# Controller.net
KiCad netlist of a schematic drawn in Altium Designer
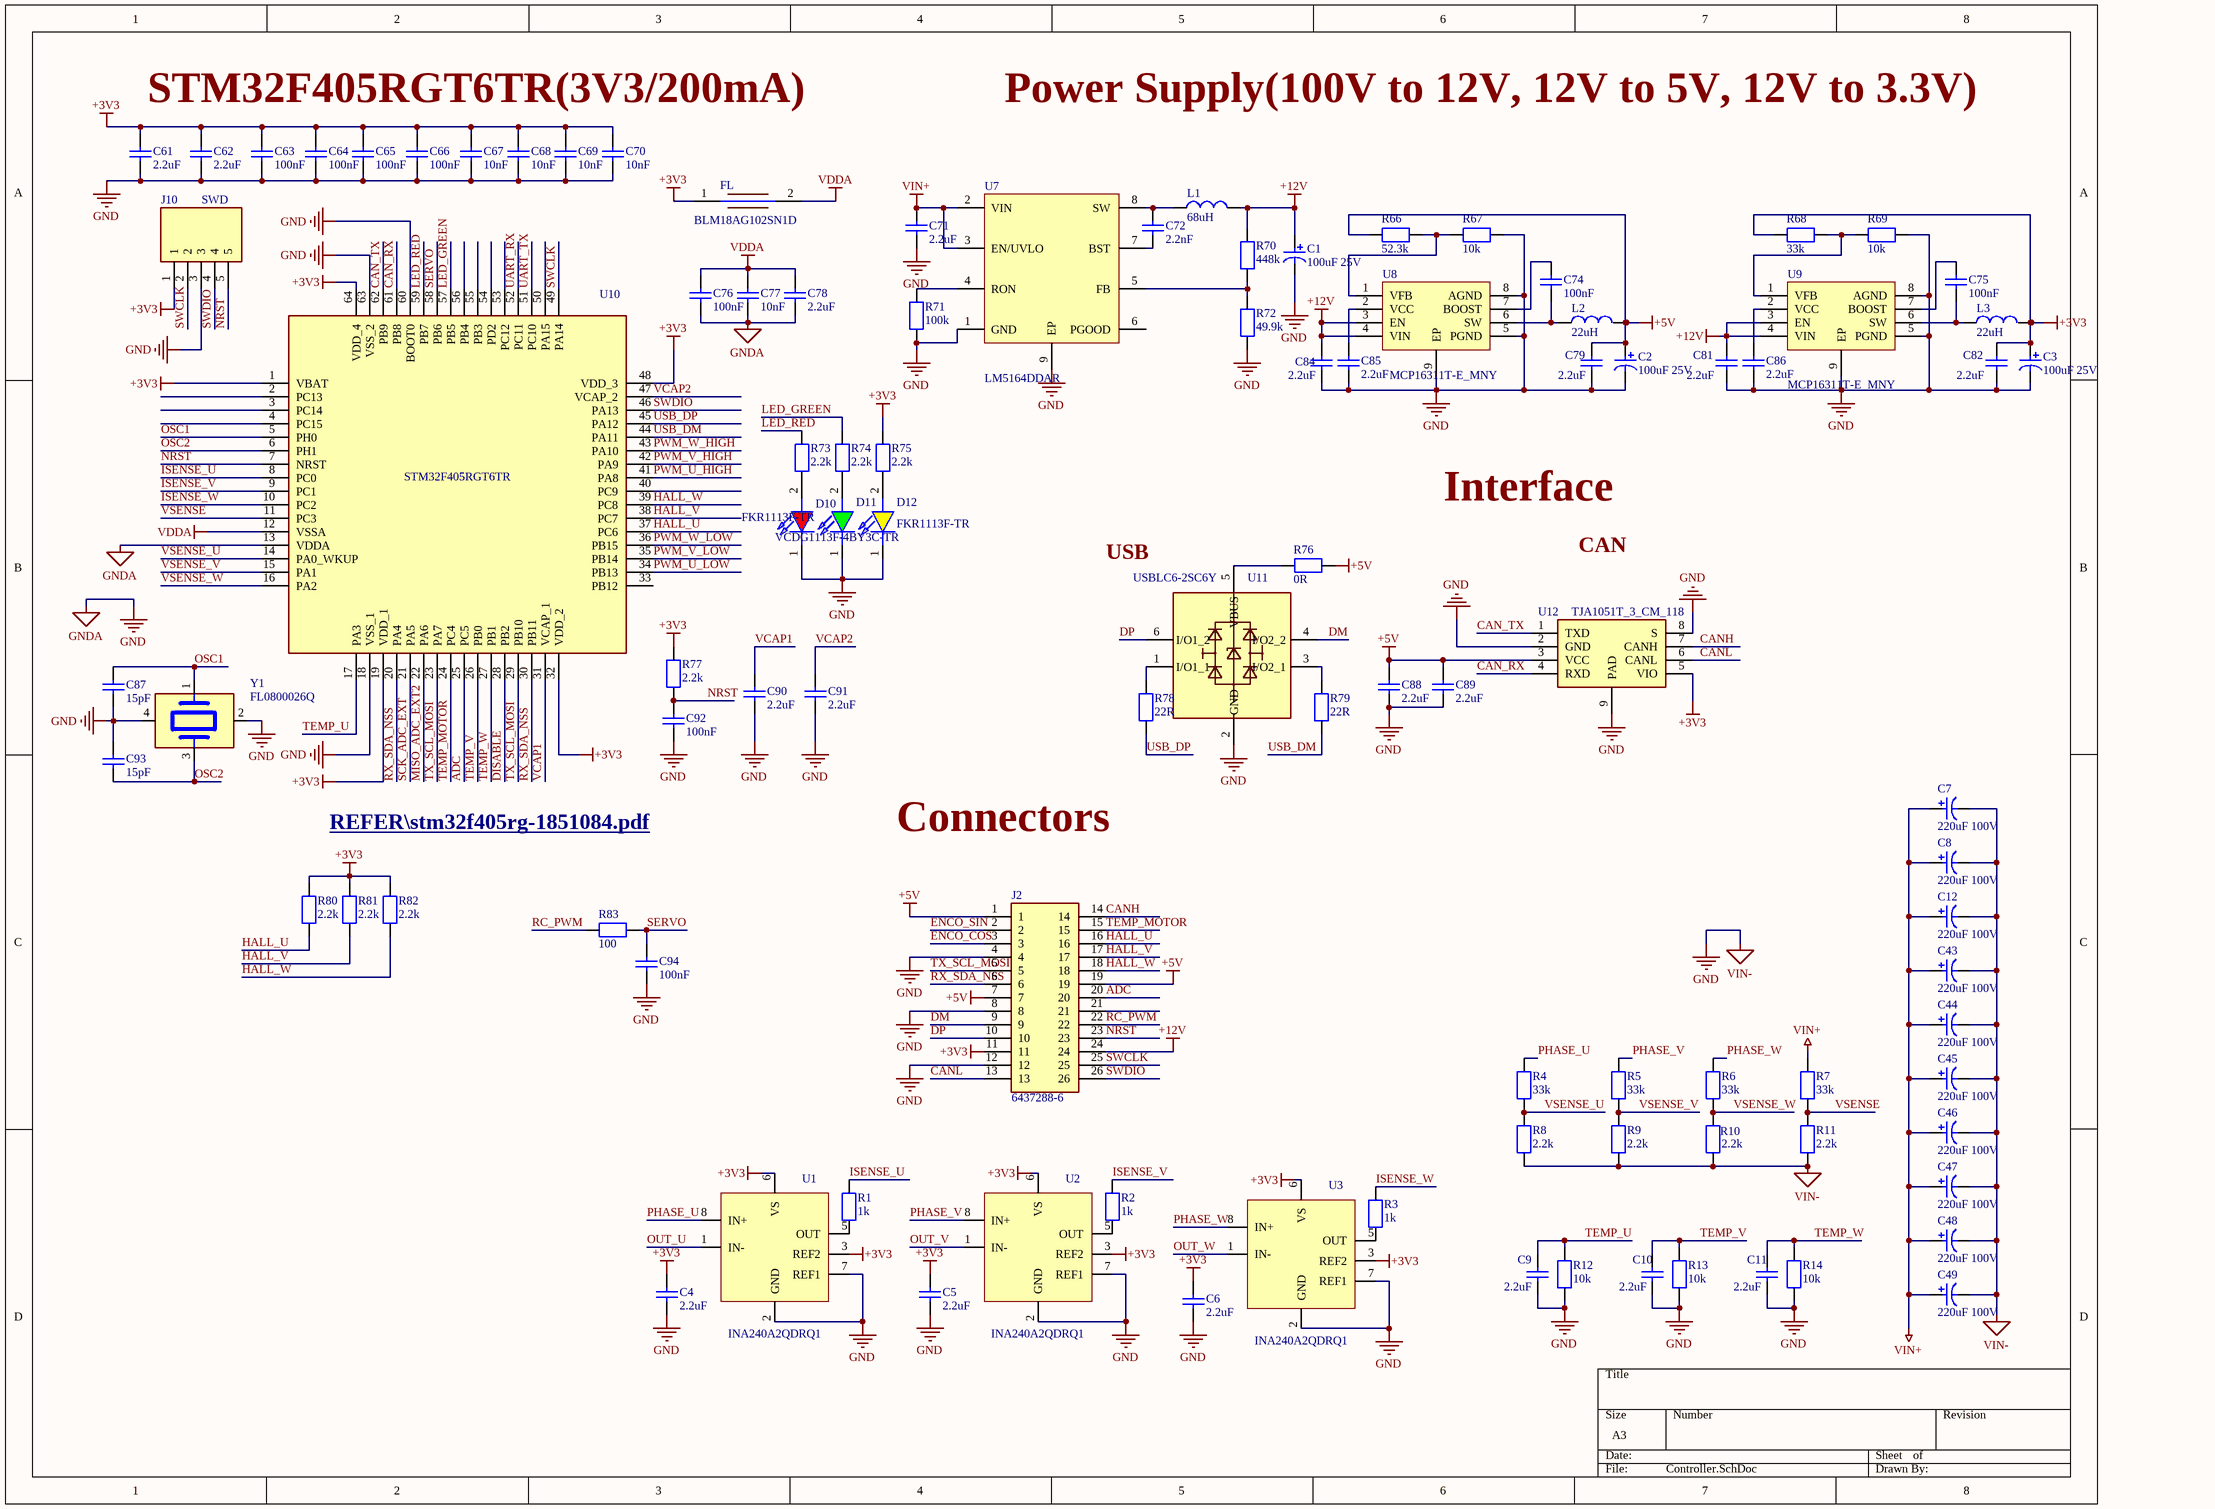
[diagram p0: Controller.SchDoc]

(export (version "E")
  (design (tool "Eeschema 10.0.6"))
  (components
    (comp (ref "C1")
      (value "100uF 25V")
      (footprint "CAPPRD250W50D630H1250")
      (description "100uF ± 10% 25V")
      (fields
        (field (name "MANUFACTURER") "Kemet")
        (field (name "MANUFACTURER PART NUMBER") "ESK107M025AE3AA")
      )
      (libsource (lib "VESC_MotorController") (part "100uF ± 10% 25V"))
    )
    (comp (ref "C2")
      (value "100uF 25V")
      (footprint "CAPPRD250W50D630H1250")
      (description "100uF ± 10% 25V")
      (fields
        (field (name "MANUFACTURER") "Kemet")
        (field (name "MANUFACTURER PART NUMBER") "ESK107M025AE3AA")
      )
      (libsource (lib "VESC_MotorController") (part "100uF ± 10% 25V"))
    )
    (comp (ref "C3")
      (value "100uF 25V")
      (footprint "CAPPRD250W50D630H1250")
      (description "100uF ± 10% 25V")
      (fields
        (field (name "MANUFACTURER") "Kemet")
        (field (name "MANUFACTURER PART NUMBER") "ESK107M025AE3AA")
      )
      (libsource (lib "VESC_MotorController") (part "100uF ± 10% 25V"))
    )
    (comp (ref "C4")
      (value "2.2uF")
      (footprint "C0603")
      (description "2.2uF ± 10% 50V")
      (fields
        (field (name "MANUFACTURER") "Yageo")
        (field (name "MANUFACTURER PART NUMBER") "GRM188R61H225ME11J")
      )
      (libsource (lib "VESC_MotorController") (part "2.2uF ± 10% 50V"))
    )
    (comp (ref "C5")
      (value "2.2uF")
      (footprint "C0603")
      (description "2.2uF ± 10% 50V")
      (fields
        (field (name "MANUFACTURER") "Yageo")
        (field (name "MANUFACTURER PART NUMBER") "GRM188R61H225ME11J")
      )
      (libsource (lib "VESC_MotorController") (part "2.2uF ± 10% 50V"))
    )
    (comp (ref "C6")
      (value "2.2uF")
      (footprint "C0603")
      (description "2.2uF ± 10% 50V")
      (fields
        (field (name "MANUFACTURER") "Yageo")
        (field (name "MANUFACTURER PART NUMBER") "GRM188R61H225ME11J")
      )
      (libsource (lib "VESC_MotorController") (part "2.2uF ± 10% 50V"))
    )
    (comp (ref "C7")
      (value "220uF 100V")
      (footprint "CAPPRD500W65D1250H2200")
      (description "Aluminum Electrolytic Capacitors - Radial Leaded Al Lytic Cap 85C Radial M Series")
      (fields
        (field (name "MANUFACTURER") "Panasonic")
        (field (name "MANUFACTURER PART NUMBER") "ECA-2AM221B")
      )
      (libsource (lib "VESC_MotorController") (part "220uF 100V"))
    )
    (comp (ref "C8")
      (value "220uF 100V")
      (footprint "CAPPRD500W65D1250H2200")
      (description "Aluminum Electrolytic Capacitors - Radial Leaded Al Lytic Cap 85C Radial M Series")
      (fields
        (field (name "MANUFACTURER") "Panasonic")
        (field (name "MANUFACTURER PART NUMBER") "ECA-2AM221B")
      )
      (libsource (lib "VESC_MotorController") (part "220uF 100V"))
    )
    (comp (ref "C9")
      (value "2.2uF")
      (footprint "C0603")
      (description "2.2uF ± 10% 50V")
      (fields
        (field (name "MANUFACTURER") "Yageo")
        (field (name "MANUFACTURER PART NUMBER") "GRM188R61H225ME11J")
      )
      (libsource (lib "VESC_MotorController") (part "2.2uF ± 10% 50V"))
    )
    (comp (ref "C10")
      (value "2.2uF")
      (footprint "C0603")
      (description "2.2uF ± 10% 50V")
      (fields
        (field (name "MANUFACTURER") "Yageo")
        (field (name "MANUFACTURER PART NUMBER") "GRM188R61H225ME11J")
      )
      (libsource (lib "VESC_MotorController") (part "2.2uF ± 10% 50V"))
    )
    (comp (ref "C11")
      (value "2.2uF")
      (footprint "C0603")
      (description "2.2uF ± 10% 50V")
      (fields
        (field (name "MANUFACTURER") "Yageo")
        (field (name "MANUFACTURER PART NUMBER") "GRM188R61H225ME11J")
      )
      (libsource (lib "VESC_MotorController") (part "2.2uF ± 10% 50V"))
    )
    (comp (ref "C12")
      (value "220uF 100V")
      (footprint "CAPPRD500W65D1250H2200")
      (description "Aluminum Electrolytic Capacitors - Radial Leaded Al Lytic Cap 85C Radial M Series")
      (fields
        (field (name "MANUFACTURER") "Panasonic")
        (field (name "MANUFACTURER PART NUMBER") "ECA-2AM221B")
      )
      (libsource (lib "VESC_MotorController") (part "220uF 100V"))
    )
    (comp (ref "C43")
      (value "220uF 100V")
      (footprint "CAPPRD500W65D1250H2200")
      (description "Aluminum Electrolytic Capacitors - Radial Leaded Al Lytic Cap 85C Radial M Series")
      (fields
        (field (name "MANUFACTURER") "Panasonic")
        (field (name "MANUFACTURER PART NUMBER") "ECA-2AM221B")
      )
      (libsource (lib "VESC_MotorController") (part "220uF 100V"))
    )
    (comp (ref "C44")
      (value "220uF 100V")
      (footprint "CAPPRD500W65D1250H2200")
      (description "Aluminum Electrolytic Capacitors - Radial Leaded Al Lytic Cap 85C Radial M Series")
      (fields
        (field (name "MANUFACTURER") "Panasonic")
        (field (name "MANUFACTURER PART NUMBER") "ECA-2AM221B")
      )
      (libsource (lib "VESC_MotorController") (part "220uF 100V"))
    )
    (comp (ref "C45")
      (value "220uF 100V")
      (footprint "CAPPRD500W65D1250H2200")
      (description "Aluminum Electrolytic Capacitors - Radial Leaded Al Lytic Cap 85C Radial M Series")
      (fields
        (field (name "MANUFACTURER") "Panasonic")
        (field (name "MANUFACTURER PART NUMBER") "ECA-2AM221B")
      )
      (libsource (lib "VESC_MotorController") (part "220uF 100V"))
    )
    (comp (ref "C46")
      (value "220uF 100V")
      (footprint "CAPPRD500W65D1250H2200")
      (description "Aluminum Electrolytic Capacitors - Radial Leaded Al Lytic Cap 85C Radial M Series")
      (fields
        (field (name "MANUFACTURER") "Panasonic")
        (field (name "MANUFACTURER PART NUMBER") "ECA-2AM221B")
      )
      (libsource (lib "VESC_MotorController") (part "220uF 100V"))
    )
    (comp (ref "C47")
      (value "220uF 100V")
      (footprint "CAPPRD500W65D1250H2200")
      (description "Aluminum Electrolytic Capacitors - Radial Leaded Al Lytic Cap 85C Radial M Series")
      (fields
        (field (name "MANUFACTURER") "Panasonic")
        (field (name "MANUFACTURER PART NUMBER") "ECA-2AM221B")
      )
      (libsource (lib "VESC_MotorController") (part "220uF 100V"))
    )
    (comp (ref "C48")
      (value "220uF 100V")
      (footprint "CAPPRD500W65D1250H2200")
      (description "Aluminum Electrolytic Capacitors - Radial Leaded Al Lytic Cap 85C Radial M Series")
      (fields
        (field (name "MANUFACTURER") "Panasonic")
        (field (name "MANUFACTURER PART NUMBER") "ECA-2AM221B")
      )
      (libsource (lib "VESC_MotorController") (part "220uF 100V"))
    )
    (comp (ref "C49")
      (value "220uF 100V")
      (footprint "CAPPRD500W65D1250H2200")
      (description "Aluminum Electrolytic Capacitors - Radial Leaded Al Lytic Cap 85C Radial M Series")
      (fields
        (field (name "MANUFACTURER") "Panasonic")
        (field (name "MANUFACTURER PART NUMBER") "ECA-2AM221B")
      )
      (libsource (lib "VESC_MotorController") (part "220uF 100V"))
    )
    (comp (ref "C61")
      (value "2.2uF")
      (footprint "C0603")
      (description "2.2uF ± 10% 50V")
      (fields
        (field (name "MANUFACTURER") "Yageo")
        (field (name "MANUFACTURER PART NUMBER") "GRM188R61H225ME11J")
      )
      (libsource (lib "VESC_MotorController") (part "2.2uF ± 10% 50V"))
    )
    (comp (ref "C62")
      (value "2.2uF")
      (footprint "C0603")
      (description "2.2uF ± 10% 50V")
      (fields
        (field (name "MANUFACTURER") "Yageo")
        (field (name "MANUFACTURER PART NUMBER") "GRM188R61H225ME11J")
      )
      (libsource (lib "VESC_MotorController") (part "2.2uF ± 10% 50V"))
    )
    (comp (ref "C63")
      (value "100nF")
      (footprint "C0603")
      (description "100nF ± 10% 50V")
      (fields
        (field (name "MANUFACTURER") "Yageo")
        (field (name "MANUFACTURER PART NUMBER") "CS0603KRX7R9BB104")
      )
      (libsource (lib "VESC_MotorController") (part "100nF ± 10% 50V"))
    )
    (comp (ref "C64")
      (value "100nF")
      (footprint "C0603")
      (description "100nF ± 10% 50V")
      (fields
        (field (name "MANUFACTURER") "Yageo")
        (field (name "MANUFACTURER PART NUMBER") "CS0603KRX7R9BB104")
      )
      (libsource (lib "VESC_MotorController") (part "100nF ± 10% 50V"))
    )
    (comp (ref "C65")
      (value "100nF")
      (footprint "C0603")
      (description "100nF ± 10% 50V")
      (fields
        (field (name "MANUFACTURER") "Yageo")
        (field (name "MANUFACTURER PART NUMBER") "CS0603KRX7R9BB104")
      )
      (libsource (lib "VESC_MotorController") (part "100nF ± 10% 50V"))
    )
    (comp (ref "C66")
      (value "100nF")
      (footprint "C0603")
      (description "100nF ± 10% 50V")
      (fields
        (field (name "MANUFACTURER") "Yageo")
        (field (name "MANUFACTURER PART NUMBER") "CS0603KRX7R9BB104")
      )
      (libsource (lib "VESC_MotorController") (part "100nF ± 10% 50V"))
    )
    (comp (ref "C67")
      (value "10nF")
      (footprint "C0603")
      (description "10nF ± 10% 50V")
      (fields
        (field (name "MANUFACTURER") "Yageo")
        (field (name "MANUFACTURER PART NUMBER") "CS0603KRX79BB103")
      )
      (libsource (lib "VESC_MotorController") (part "10nF ± 10% 50V"))
    )
    (comp (ref "C68")
      (value "10nF")
      (footprint "C0603")
      (description "10nF ± 10% 50V")
      (fields
        (field (name "MANUFACTURER") "Yageo")
        (field (name "MANUFACTURER PART NUMBER") "CS0603KRX79BB103")
      )
      (libsource (lib "VESC_MotorController") (part "10nF ± 10% 50V"))
    )
    (comp (ref "C69")
      (value "10nF")
      (footprint "C0603")
      (description "10nF ± 10% 50V")
      (fields
        (field (name "MANUFACTURER") "Yageo")
        (field (name "MANUFACTURER PART NUMBER") "CS0603KRX79BB103")
      )
      (libsource (lib "VESC_MotorController") (part "10nF ± 10% 50V"))
    )
    (comp (ref "C70")
      (value "10nF")
      (footprint "C0603")
      (description "10nF ± 10% 50V")
      (fields
        (field (name "MANUFACTURER") "Yageo")
        (field (name "MANUFACTURER PART NUMBER") "CS0603KRX79BB103")
      )
      (libsource (lib "VESC_MotorController") (part "10nF ± 10% 50V"))
    )
    (comp (ref "C71")
      (value "2.2uF")
      (footprint "C0603")
      (description "2.2uF ± 10% 50V")
      (fields
        (field (name "MANUFACTURER") "Yageo")
        (field (name "MANUFACTURER PART NUMBER") "GRM188R61H225ME11J")
      )
      (libsource (lib "VESC_MotorController") (part "2.2uF ± 10% 50V"))
    )
    (comp (ref "C72")
      (value "2.2nF")
      (footprint "C0603")
      (description "2.2nF ± 10% 50V")
      (fields
        (field (name "MANUFACTURER") "Yageo")
        (field (name "MANUFACTURER PART NUMBER") "CS0603KRX79BB222")
      )
      (libsource (lib "VESC_MotorController") (part "2.2nF ± 10% 50V"))
    )
    (comp (ref "C74")
      (value "100nF")
      (footprint "C0603")
      (description "100nF ± 10% 50V")
      (fields
        (field (name "MANUFACTURER") "Yageo")
        (field (name "MANUFACTURER PART NUMBER") "CS0603KRX7R9BB104")
      )
      (libsource (lib "VESC_MotorController") (part "100nF ± 10% 50V"))
    )
    (comp (ref "C75")
      (value "100nF")
      (footprint "C0603")
      (description "100nF ± 10% 50V")
      (fields
        (field (name "MANUFACTURER") "Yageo")
        (field (name "MANUFACTURER PART NUMBER") "CS0603KRX7R9BB104")
      )
      (libsource (lib "VESC_MotorController") (part "100nF ± 10% 50V"))
    )
    (comp (ref "C76")
      (value "100nF")
      (footprint "C0603")
      (description "100nF ± 10% 50V")
      (fields
        (field (name "MANUFACTURER") "Yageo")
        (field (name "MANUFACTURER PART NUMBER") "CS0603KRX7R9BB104")
      )
      (libsource (lib "VESC_MotorController") (part "100nF ± 10% 50V"))
    )
    (comp (ref "C77")
      (value "10nF")
      (footprint "C0603")
      (description "10nF ± 10% 50V")
      (fields
        (field (name "MANUFACTURER") "Yageo")
        (field (name "MANUFACTURER PART NUMBER") "CS0603KRX79BB103")
      )
      (libsource (lib "VESC_MotorController") (part "10nF ± 10% 50V"))
    )
    (comp (ref "C78")
      (value "2.2uF")
      (footprint "C0603")
      (description "2.2uF ± 10% 50V")
      (fields
        (field (name "MANUFACTURER") "Yageo")
        (field (name "MANUFACTURER PART NUMBER") "GRM188R61H225ME11J")
      )
      (libsource (lib "VESC_MotorController") (part "2.2uF ± 10% 50V"))
    )
    (comp (ref "C79")
      (value "2.2uF")
      (footprint "C0603")
      (description "2.2uF ± 10% 50V")
      (fields
        (field (name "MANUFACTURER") "Yageo")
        (field (name "MANUFACTURER PART NUMBER") "GRM188R61H225ME11J")
      )
      (libsource (lib "VESC_MotorController") (part "2.2uF ± 10% 50V"))
    )
    (comp (ref "C81")
      (value "2.2uF")
      (footprint "C0603")
      (description "2.2uF ± 10% 50V")
      (fields
        (field (name "MANUFACTURER") "Yageo")
        (field (name "MANUFACTURER PART NUMBER") "GRM188R61H225ME11J")
      )
      (libsource (lib "VESC_MotorController") (part "2.2uF ± 10% 50V"))
    )
    (comp (ref "C82")
      (value "2.2uF")
      (footprint "C0603")
      (description "2.2uF ± 10% 50V")
      (fields
        (field (name "MANUFACTURER") "Yageo")
        (field (name "MANUFACTURER PART NUMBER") "GRM188R61H225ME11J")
      )
      (libsource (lib "VESC_MotorController") (part "2.2uF ± 10% 50V"))
    )
    (comp (ref "C84")
      (value "2.2uF")
      (footprint "C0603")
      (description "2.2uF ± 10% 50V")
      (fields
        (field (name "MANUFACTURER") "Yageo")
        (field (name "MANUFACTURER PART NUMBER") "GRM188R61H225ME11J")
      )
      (libsource (lib "VESC_MotorController") (part "2.2uF ± 10% 50V"))
    )
    (comp (ref "C85")
      (value "2.2uF")
      (footprint "C0603")
      (description "2.2uF ± 10% 50V")
      (fields
        (field (name "MANUFACTURER") "Yageo")
        (field (name "MANUFACTURER PART NUMBER") "GRM188R61H225ME11J")
      )
      (libsource (lib "VESC_MotorController") (part "2.2uF ± 10% 50V"))
    )
    (comp (ref "C86")
      (value "2.2uF")
      (footprint "C0603")
      (description "2.2uF ± 10% 50V")
      (fields
        (field (name "MANUFACTURER") "Yageo")
        (field (name "MANUFACTURER PART NUMBER") "GRM188R61H225ME11J")
      )
      (libsource (lib "VESC_MotorController") (part "2.2uF ± 10% 50V"))
    )
    (comp (ref "C87")
      (value "15pF")
      (footprint "C0402")
      (description "15pF ± 10% 50V")
      (fields
        (field (name "MANUFACTURER") "Yageo")
        (field (name "MANUFACTURER PART NUMBER") "CS0603KRX79BB150")
      )
      (libsource (lib "VESC_MotorController") (part "15pF ± 10% 50V"))
    )
    (comp (ref "C88")
      (value "2.2uF")
      (footprint "C0603")
      (description "2.2uF ± 10% 50V")
      (fields
        (field (name "MANUFACTURER") "Yageo")
        (field (name "MANUFACTURER PART NUMBER") "GRM188R61H225ME11J")
      )
      (libsource (lib "VESC_MotorController") (part "2.2uF ± 10% 50V"))
    )
    (comp (ref "C89")
      (value "2.2uF")
      (footprint "C0603")
      (description "2.2uF ± 10% 50V")
      (fields
        (field (name "MANUFACTURER") "Yageo")
        (field (name "MANUFACTURER PART NUMBER") "GRM188R61H225ME11J")
      )
      (libsource (lib "VESC_MotorController") (part "2.2uF ± 10% 50V"))
    )
    (comp (ref "C90")
      (value "2.2uF")
      (footprint "C0603")
      (description "2.2uF ± 10% 50V")
      (fields
        (field (name "MANUFACTURER") "Yageo")
        (field (name "MANUFACTURER PART NUMBER") "GRM188R61H225ME11J")
      )
      (libsource (lib "VESC_MotorController") (part "2.2uF ± 10% 50V"))
    )
    (comp (ref "C91")
      (value "2.2uF")
      (footprint "C0603")
      (description "2.2uF ± 10% 50V")
      (fields
        (field (name "MANUFACTURER") "Yageo")
        (field (name "MANUFACTURER PART NUMBER") "GRM188R61H225ME11J")
      )
      (libsource (lib "VESC_MotorController") (part "2.2uF ± 10% 50V"))
    )
    (comp (ref "C92")
      (value "100nF")
      (footprint "C0603")
      (description "100nF ± 10% 50V")
      (fields
        (field (name "MANUFACTURER") "Yageo")
        (field (name "MANUFACTURER PART NUMBER") "CS0603KRX7R9BB104")
      )
      (libsource (lib "VESC_MotorController") (part "100nF ± 10% 50V"))
    )
    (comp (ref "C93")
      (value "15pF")
      (footprint "C0402")
      (description "15pF ± 10% 50V")
      (fields
        (field (name "MANUFACTURER") "Yageo")
        (field (name "MANUFACTURER PART NUMBER") "CS0603KRX79BB150")
      )
      (libsource (lib "VESC_MotorController") (part "15pF ± 10% 50V"))
    )
    (comp (ref "C94")
      (value "100nF")
      (footprint "C0603")
      (description "100nF ± 10% 50V")
      (fields
        (field (name "MANUFACTURER") "Yageo")
        (field (name "MANUFACTURER PART NUMBER") "CS0603KRX7R9BB104")
      )
      (libsource (lib "VESC_MotorController") (part "100nF ± 10% 50V"))
    )
    (comp (ref "D10")
      (value "FKR1113F-TR")
      (footprint "VCDG1113F4BY3CTR")
      (description "R/A LED")
      (fields (field (name "MANUFACTURER") "Stanley Electric"))
      (libsource (lib "VESC_MotorController") (part "LED_RED"))
    )
    (comp (ref "D11")
      (value "VCDG1113F-4BY3C-TR")
      (footprint "VCDG1113F4BY3CTR")
      (description "R/A LED")
      (fields (field (name "MANUFACTURER") "Stanley Electric"))
      (libsource (lib "VESC_MotorController") (part "LED_GREEN"))
    )
    (comp (ref "D12")
      (value "FKR1113F-TR")
      (footprint "VCDG1113F4BY3CTR")
      (description "R/A LED")
      (fields
        (field (name "MANUFACTURER") "Stanley Electric")
        (field (name "MANUFACTURER PART NUMBER") "FKY1113F-TR")
      )
      (libsource (lib "VESC_MotorController") (part "LED_YELLOW"))
    )
    (comp (ref "FL")
      (value "BLM18AG102SN1D")
      (footprint "BLM18EG121SH1D")
      (description "Ferrite Beads 1000 OHM 25% Alternate Sizing Guide Below")
      (fields (field (name "MANUFACTURER") "Murata"))
      (libsource (lib "VESC_MotorController") (part "BLM18AG102SN1D"))
    )
    (comp (ref "J2")
      (value "6437288-6")
      (footprint "64372886")
      (description "Header vert 26 way 4 row Tab Superseal")
      (fields (field (name "MANUFACTURER") "TE Connectivity"))
      (libsource (lib "VESC_MotorController") (part "6437288-6"))
    )
    (comp (ref "J10")
      (value "SWD")
      (footprint "61300511021")
      (description "Headers & Wire Housings WR-PHD 2.54mm Hdr 5P Single RA Gold")
      (fields
        (field (name "MANUFACTURER") "Wurth Electronic")
        (field (name "MANUFACTURER PART NUMBER") "61300511021")
      )
      (libsource (lib "VESC_MotorController") (part "Header 5 Pin_1"))
    )
    (comp (ref "L1")
      (value "68uH")
      (footprint "INDPM7973X540N")
      (description "Ind,7.9x7.3x5.2mm,68uH+/-20%,2.7A,shd")
      (fields
        (field (name "MANUFACTURER") "Bourns")
        (field (name "MANUFACTURER PART NUMBER") "SRP7050WA-680M")
      )
      (libsource (lib "VESC_MotorController") (part "SRP7050WA-680M"))
    )
    (comp (ref "L2")
      (value "22uH")
      (footprint "INDPM7973X540N")
      (description "Ind,7.9x7.3x5.2mm,22uH+/-20%,5A,shd")
      (fields
        (field (name "MANUFACTURER") "Bourns")
        (field (name "MANUFACTURER PART NUMBER") "SRP7050WA-220M")
      )
      (libsource (lib "VESC_MotorController") (part "SRP7050WA-220M"))
    )
    (comp (ref "L3")
      (value "22uH")
      (footprint "INDPM7973X540N")
      (description "Ind,7.9x7.3x5.2mm,22uH+/-20%,5A,shd")
      (fields
        (field (name "MANUFACTURER") "Bourns")
        (field (name "MANUFACTURER PART NUMBER") "SRP7050WA-220M")
      )
      (libsource (lib "VESC_MotorController") (part "SRP7050WA-220M"))
    )
    (comp (ref "R1")
      (value "1k")
      (footprint "R0603")
      (description "1 kOhms ±1% 0.1W")
      (fields
        (field (name "MANUFACTURER") "Yageo")
        (field (name "MANUFACTURER PART NUMBER") "RC0603FR-071KL")
      )
      (libsource (lib "VESC_MotorController") (part "1 kOhms ±1% 0.1W"))
    )
    (comp (ref "R2")
      (value "1k")
      (footprint "R0603")
      (description "1 kOhms ±1% 0.1W")
      (fields
        (field (name "MANUFACTURER") "Yageo")
        (field (name "MANUFACTURER PART NUMBER") "RC0603FR-071KL")
      )
      (libsource (lib "VESC_MotorController") (part "1 kOhms ±1% 0.1W"))
    )
    (comp (ref "R3")
      (value "1k")
      (footprint "R0603")
      (description "1 kOhms ±1% 0.1W")
      (fields
        (field (name "MANUFACTURER") "Yageo")
        (field (name "MANUFACTURER PART NUMBER") "RC0603FR-071KL")
      )
      (libsource (lib "VESC_MotorController") (part "1 kOhms ±1% 0.1W"))
    )
    (comp (ref "R4")
      (value "33k")
      (footprint "R0603")
      (description "33 kOhms ±1% 0.1W")
      (fields
        (field (name "MANUFACTURER") "Yageo")
        (field (name "MANUFACTURER PART NUMBER") "RC0603FR-0733KL")
      )
      (libsource (lib "VESC_MotorController") (part "33 kOhms ±1% 0.1W"))
    )
    (comp (ref "R5")
      (value "33k")
      (footprint "R0603")
      (description "33 kOhms ±1% 0.1W")
      (fields
        (field (name "MANUFACTURER") "Yageo")
        (field (name "MANUFACTURER PART NUMBER") "RC0603FR-0733KL")
      )
      (libsource (lib "VESC_MotorController") (part "33 kOhms ±1% 0.1W"))
    )
    (comp (ref "R6")
      (value "33k")
      (footprint "R0603")
      (description "33 kOhms ±1% 0.1W")
      (fields
        (field (name "MANUFACTURER") "Yageo")
        (field (name "MANUFACTURER PART NUMBER") "RC0603FR-0733KL")
      )
      (libsource (lib "VESC_MotorController") (part "33 kOhms ±1% 0.1W"))
    )
    (comp (ref "R7")
      (value "33k")
      (footprint "R0603")
      (description "33 kOhms ±1% 0.1W")
      (fields
        (field (name "MANUFACTURER") "Yageo")
        (field (name "MANUFACTURER PART NUMBER") "RC0603FR-0733KL")
      )
      (libsource (lib "VESC_MotorController") (part "33 kOhms ±1% 0.1W"))
    )
    (comp (ref "R8")
      (value "2.2k")
      (footprint "R0603")
      (description "2.2 kOhms ±1% 0.1W")
      (fields
        (field (name "MANUFACTURER") "Yageo")
        (field (name "MANUFACTURER PART NUMBER") "RC0603FR-072K2L")
      )
      (libsource (lib "VESC_MotorController") (part "2.2 kOhms ±1% 0.1W"))
    )
    (comp (ref "R9")
      (value "2.2k")
      (footprint "R0603")
      (description "2.2 kOhms ±1% 0.1W")
      (fields
        (field (name "MANUFACTURER") "Yageo")
        (field (name "MANUFACTURER PART NUMBER") "RC0603FR-072K2L")
      )
      (libsource (lib "VESC_MotorController") (part "2.2 kOhms ±1% 0.1W"))
    )
    (comp (ref "R10")
      (value "2.2k")
      (footprint "R0603")
      (description "2.2 kOhms ±1% 0.1W")
      (fields
        (field (name "MANUFACTURER") "Yageo")
        (field (name "MANUFACTURER PART NUMBER") "RC0603FR-072K2L")
      )
      (libsource (lib "VESC_MotorController") (part "2.2 kOhms ±1% 0.1W"))
    )
    (comp (ref "R11")
      (value "2.2k")
      (footprint "R0603")
      (description "2.2 kOhms ±1% 0.1W")
      (fields
        (field (name "MANUFACTURER") "Yageo")
        (field (name "MANUFACTURER PART NUMBER") "RC0603FR-072K2L")
      )
      (libsource (lib "VESC_MotorController") (part "2.2 kOhms ±1% 0.1W"))
    )
    (comp (ref "R12")
      (value "10k")
      (footprint "R0603")
      (description "10 kOhms ±1% 0.1W")
      (fields
        (field (name "MANUFACTURER") "Yageo")
        (field (name "MANUFACTURER PART NUMBER") "RC0603FR-0710KL")
      )
      (libsource (lib "VESC_MotorController") (part "10 kOhms ±1% 0.1W"))
    )
    (comp (ref "R13")
      (value "10k")
      (footprint "R0603")
      (description "10 kOhms ±1% 0.1W")
      (fields
        (field (name "MANUFACTURER") "Yageo")
        (field (name "MANUFACTURER PART NUMBER") "RC0603FR-0710KL")
      )
      (libsource (lib "VESC_MotorController") (part "10 kOhms ±1% 0.1W"))
    )
    (comp (ref "R14")
      (value "10k")
      (footprint "R0603")
      (description "10 kOhms ±1% 0.1W")
      (fields
        (field (name "MANUFACTURER") "Yageo")
        (field (name "MANUFACTURER PART NUMBER") "RC0603FR-0710KL")
      )
      (libsource (lib "VESC_MotorController") (part "10 kOhms ±1% 0.1W"))
    )
    (comp (ref "R66")
      (value "52.3k")
      (footprint "R0603")
      (description "52.3 kOhms ±1% 0.1W")
      (fields
        (field (name "MANUFACTURER") "Yageo")
        (field (name "MANUFACTURER PART NUMBER") "RC0603FR-0752K3L")
      )
      (libsource (lib "VESC_MotorController") (part "52.3 kOhms ±1% 0.1W"))
    )
    (comp (ref "R67")
      (value "10k")
      (footprint "R0603")
      (description "10 kOhms ±1% 0.1W")
      (fields
        (field (name "MANUFACTURER") "Yageo")
        (field (name "MANUFACTURER PART NUMBER") "RC0603FR-0710KL")
      )
      (libsource (lib "VESC_MotorController") (part "10 kOhms ±1% 0.1W"))
    )
    (comp (ref "R68")
      (value "33k")
      (footprint "R0603")
      (description "33 kOhms ±1% 0.1W")
      (fields
        (field (name "MANUFACTURER") "Yageo")
        (field (name "MANUFACTURER PART NUMBER") "RC0603FR-0733KL")
      )
      (libsource (lib "VESC_MotorController") (part "33 kOhms ±1% 0.1W"))
    )
    (comp (ref "R69")
      (value "10k")
      (footprint "R0603")
      (description "10 kOhms ±1% 0.1W")
      (fields
        (field (name "MANUFACTURER") "Yageo")
        (field (name "MANUFACTURER PART NUMBER") "RC0603FR-0710KL")
      )
      (libsource (lib "VESC_MotorController") (part "10 kOhms ±1% 0.1W"))
    )
    (comp (ref "R70")
      (value "448k")
      (footprint "R0603")
      (description "448 kOhms ±1% 0.1W")
      (fields
        (field (name "MANUFACTURER") "Yageo")
        (field (name "MANUFACTURER PART NUMBER") "RC0603FR-07448KL")
      )
      (libsource (lib "VESC_MotorController") (part "448 kOhms ±1% 0.1W"))
    )
    (comp (ref "R71")
      (value "100k")
      (footprint "R0603")
      (description "100 kOhms ±1% 0.1W")
      (fields
        (field (name "MANUFACTURER") "Yageo")
        (field (name "MANUFACTURER PART NUMBER") "RC0603FR-07100KL")
      )
      (libsource (lib "VESC_MotorController") (part "100 kOhms ±1% 0.1W"))
    )
    (comp (ref "R72")
      (value "49.9k")
      (footprint "R0603")
      (description "49.9 kOhms ±1% 0.1W")
      (fields
        (field (name "MANUFACTURER") "Yageo")
        (field (name "MANUFACTURER PART NUMBER") "RC0603FR-0749K9L")
      )
      (libsource (lib "VESC_MotorController") (part "49.9 kOhms ±1% 0.1W"))
    )
    (comp (ref "R73")
      (value "2.2k")
      (footprint "R0603")
      (description "2.2 kOhms ±1% 0.1W")
      (fields
        (field (name "MANUFACTURER") "Yageo")
        (field (name "MANUFACTURER PART NUMBER") "RC0603FR-072K2L")
      )
      (libsource (lib "VESC_MotorController") (part "2.2 kOhms ±1% 0.1W"))
    )
    (comp (ref "R74")
      (value "2.2k")
      (footprint "R0603")
      (description "2.2 kOhms ±1% 0.1W")
      (fields
        (field (name "MANUFACTURER") "Yageo")
        (field (name "MANUFACTURER PART NUMBER") "RC0603FR-072K2L")
      )
      (libsource (lib "VESC_MotorController") (part "2.2 kOhms ±1% 0.1W"))
    )
    (comp (ref "R75")
      (value "2.2k")
      (footprint "R0603")
      (description "2.2 kOhms ±1% 0.1W")
      (fields
        (field (name "MANUFACTURER") "Yageo")
        (field (name "MANUFACTURER PART NUMBER") "RC0603FR-072K2L")
      )
      (libsource (lib "VESC_MotorController") (part "2.2 kOhms ±1% 0.1W"))
    )
    (comp (ref "R76")
      (value "0R")
      (footprint "R1206")
      (description "0 ohm 0.25W ±1%")
      (fields
        (field (name "MANUFACTURER PART NUMBER") "RC1206FR-070RL")
        (field (name "MANUFACTURER") "Yageo")
      )
      (libsource (lib "VESC_MotorController") (part "0ohm 0.25W ±1%"))
    )
    (comp (ref "R77")
      (value "2.2k")
      (footprint "R0603")
      (description "2.2 kOhms ±1% 0.1W")
      (fields
        (field (name "MANUFACTURER") "Yageo")
        (field (name "MANUFACTURER PART NUMBER") "RC0603FR-072K2L")
      )
      (libsource (lib "VESC_MotorController") (part "2.2 kOhms ±1% 0.1W"))
    )
    (comp (ref "R78")
      (value "22R")
      (footprint "R0603")
      (description "22 ohm 0.1W ±1%")
      (fields
        (field (name "MANUFACTURER PART NUMBER") "RC0603FR-0722RL")
        (field (name "MANUFACTURER") "Yageo")
      )
      (libsource (lib "VESC_MotorController") (part "22ohm 0.1W ±1%"))
    )
    (comp (ref "R79")
      (value "22R")
      (footprint "R0603")
      (description "22 ohm 0.1W ±1%")
      (fields
        (field (name "MANUFACTURER PART NUMBER") "RC0603FR-0722RL")
        (field (name "MANUFACTURER") "Yageo")
      )
      (libsource (lib "VESC_MotorController") (part "22ohm 0.1W ±1%"))
    )
    (comp (ref "R80")
      (value "2.2k")
      (footprint "R0603")
      (description "2.2 kOhms ±1% 0.1W")
      (fields
        (field (name "MANUFACTURER") "Yageo")
        (field (name "MANUFACTURER PART NUMBER") "RC0603FR-072K2L")
      )
      (libsource (lib "VESC_MotorController") (part "2.2 kOhms ±1% 0.1W"))
    )
    (comp (ref "R81")
      (value "2.2k")
      (footprint "R0603")
      (description "2.2 kOhms ±1% 0.1W")
      (fields
        (field (name "MANUFACTURER") "Yageo")
        (field (name "MANUFACTURER PART NUMBER") "RC0603FR-072K2L")
      )
      (libsource (lib "VESC_MotorController") (part "2.2 kOhms ±1% 0.1W"))
    )
    (comp (ref "R82")
      (value "2.2k")
      (footprint "R0603")
      (description "2.2 kOhms ±1% 0.1W")
      (fields
        (field (name "MANUFACTURER") "Yageo")
        (field (name "MANUFACTURER PART NUMBER") "RC0603FR-072K2L")
      )
      (libsource (lib "VESC_MotorController") (part "2.2 kOhms ±1% 0.1W"))
    )
    (comp (ref "R83")
      (value "100")
      (footprint "R0603")
      (description "100 Ohms ±1% 0.1W")
      (fields
        (field (name "MANUFACTURER") "Yageo")
        (field (name "MANUFACTURER PART NUMBER") "RC0603FR-0710KL")
      )
      (libsource (lib "VESC_MotorController") (part "100 Ohms ±1% 0.1W"))
    )
    (comp (ref "U1")
      (value "INA240A2QDRQ1")
      (footprint "SOIC127P600X175-8N")
      (description "Automotive, High/Low Side, Bi-Directional Zer-Drift Current Sense Amp w/ Enhanced PWM Rejection")
      (fields (field (name "MANUFACTURER") "Texas Instruments"))
      (libsource (lib "VESC_MotorController") (part "INA240A2QDRQ1"))
    )
    (comp (ref "U2")
      (value "INA240A2QDRQ1")
      (footprint "SOIC127P600X175-8N")
      (description "Automotive, High/Low Side, Bi-Directional Zer-Drift Current Sense Amp w/ Enhanced PWM Rejection")
      (fields (field (name "MANUFACTURER") "Texas Instruments"))
      (libsource (lib "VESC_MotorController") (part "INA240A2QDRQ1"))
    )
    (comp (ref "U3")
      (value "INA240A2QDRQ1")
      (footprint "SOIC127P600X175-8N")
      (description "Automotive, High/Low Side, Bi-Directional Zer-Drift Current Sense Amp w/ Enhanced PWM Rejection")
      (fields (field (name "MANUFACTURER") "Texas Instruments"))
      (libsource (lib "VESC_MotorController") (part "INA240A2QDRQ1"))
    )
    (comp (ref "U7")
      (value "LM5164DDAR")
      (footprint "SOIC-8(EPAD)")
      (fields (field (name "MANUFACTURER") "Texas Instruments"))
      (libsource (lib "VESC_MotorController") (part "LM5164DDAR"))
    )
    (comp (ref "U8")
      (value "MCP16311T-E_MNY")
      (footprint "MSOP-8")
      (description "Microchip, MCP16311T-E/MNY Step Down DC-DC Converter 1A Adjustable, 2  24 V 8-Pin, TDFN")
      (fields
        (field (name "MANUFACTURER") "Microchip")
        (field (name "MANUFACTURER PART NUMBER") "MCP16311T-E/MNY")
      )
      (libsource (lib "VESC_MotorController") (part "MCP16311T-E_MNY"))
    )
    (comp (ref "U9")
      (value "MCP16311T-E_MNY")
      (footprint "MSOP-8")
      (description "Microchip, MCP16311T-E/MNY Step Down DC-DC Converter 1A Adjustable, 2  24 V 8-Pin, TDFN")
      (fields
        (field (name "MANUFACTURER") "Microchip")
        (field (name "MANUFACTURER PART NUMBER") "MCP16311T-E/MNY")
      )
      (libsource (lib "VESC_MotorController") (part "MCP16311T-E_MNY"))
    )
    (comp (ref "U10")
      (value "STM32F405RGT6TR")
      (footprint "QFP50P1200X1200X160-64N")
      (fields (field (name "MOUSER PART NUMBER") "511-STM32F405RGT6TR"))
      (libsource (lib "STM32F405RGT6TR") (part "STM32F405RGT6TR"))
    )
    (comp (ref "U11")
      (value "USBLC6-2SC6Y")
      (footprint "SOT95P280X145-6N")
      (fields (field (name "MANUFACTURER") "STMicroelectronics"))
      (libsource (lib "VESC_MotorController") (part "USBLC6-2SC6Y"))
    )
    (comp (ref "U12")
      (value "TJA1051T_3_CM_118")
      (footprint "SOIC127P600X175-8N")
      (description "CAN Interface IC BL Advanced Automotive Analog")
      (fields
        (field (name "MANUFACTURER") "NXP Semiconductors")
        (field (name "MANUFACTURER PART NUMBER") "TJA1051T/3/CM,118")
      )
      (libsource (lib "VESC_MotorController") (part "TJA1051T_3_CM_118"))
    )
    (comp (ref "Y1")
      (value "FL0800026Q")
      (footprint "XTAL_FL0800026Q")
      (description "8 MHz A±30ppm Crystals Crystal Ceramic SEAM3225 T&R 3K")
      (fields (field (name "MANUFACTURER") "Diodes Incorporated"))
      (libsource (lib "VESC_MotorController") (part "FL0800026Q"))
    )
  )
  (nets
    (net (code "1") (name "+3V3") (class "Default")
      (node (ref "C3") (pin "1") (pinfunction "1_1") (pintype "passive"))
      (node (ref "C4") (pin "2") (pinfunction "2_2") (pintype "passive"))
      (node (ref "C5") (pin "2") (pinfunction "2_2") (pintype "passive"))
      (node (ref "C6") (pin "2") (pinfunction "2_2") (pintype "passive"))
      (node (ref "C61") (pin "2") (pinfunction "2_2") (pintype "passive"))
      (node (ref "C62") (pin "2") (pinfunction "2_2") (pintype "passive"))
      (node (ref "C63") (pin "2") (pinfunction "2_2") (pintype "passive"))
      (node (ref "C64") (pin "2") (pinfunction "2_2") (pintype "passive"))
      (node (ref "C65") (pin "2") (pinfunction "2_2") (pintype "passive"))
      (node (ref "C66") (pin "2") (pinfunction "2_2") (pintype "passive"))
      (node (ref "C67") (pin "2") (pinfunction "2_2") (pintype "passive"))
      (node (ref "C68") (pin "2") (pinfunction "2_2") (pintype "passive"))
      (node (ref "C69") (pin "2") (pinfunction "2_2") (pintype "passive"))
      (node (ref "C70") (pin "2") (pinfunction "2_2") (pintype "passive"))
      (node (ref "C82") (pin "2") (pinfunction "2_2") (pintype "passive"))
      (node (ref "FL") (pin "1") (pinfunction "1_1") (pintype "passive"))
      (node (ref "J10") (pin "1") (pinfunction "1_1") (pintype "passive"))
      (node (ref "J2") (pin "11") (pinfunction "11_11") (pintype "passive"))
      (node (ref "L3") (pin "2") (pinfunction "2_2") (pintype "passive"))
      (node (ref "R68") (pin "1") (pinfunction "1_1") (pintype "passive"))
      (node (ref "R75") (pin "2") (pinfunction "2_2") (pintype "passive"))
      (node (ref "R77") (pin "2") (pinfunction "2_2") (pintype "passive"))
      (node (ref "R80") (pin "2") (pinfunction "2_2") (pintype "passive"))
      (node (ref "R81") (pin "2") (pinfunction "2_2") (pintype "passive"))
      (node (ref "R82") (pin "2") (pinfunction "2_2") (pintype "passive"))
      (node (ref "U1") (pin "3") (pinfunction "REF2_3") (pintype "passive"))
      (node (ref "U1") (pin "6") (pinfunction "VS_6") (pintype "passive"))
      (node (ref "U10") (pin "1") (pinfunction "VBAT_1") (pintype "passive"))
      (node (ref "U10") (pin "19") (pinfunction "VDD_1_19") (pintype "passive"))
      (node (ref "U10") (pin "32") (pinfunction "VDD_2_32") (pintype "passive"))
      (node (ref "U10") (pin "48") (pinfunction "VDD_3_48") (pintype "passive"))
      (node (ref "U10") (pin "64") (pinfunction "VDD_4_64") (pintype "passive"))
      (node (ref "U12") (pin "5") (pinfunction "VIO_5") (pintype "passive"))
      (node (ref "U2") (pin "3") (pinfunction "REF2_3") (pintype "passive"))
      (node (ref "U2") (pin "6") (pinfunction "VS_6") (pintype "passive"))
      (node (ref "U3") (pin "3") (pinfunction "REF2_3") (pintype "passive"))
      (node (ref "U3") (pin "6") (pinfunction "VS_6") (pintype "passive"))
    )
    (net (code "2") (name "+5V") (class "Default")
      (node (ref "C2") (pin "1") (pinfunction "1_1") (pintype "passive"))
      (node (ref "C79") (pin "2") (pinfunction "2_2") (pintype "passive"))
      (node (ref "C88") (pin "2") (pinfunction "2_2") (pintype "passive"))
      (node (ref "C89") (pin "2") (pinfunction "2_2") (pintype "passive"))
      (node (ref "J2") (pin "1") (pinfunction "1_1") (pintype "passive"))
      (node (ref "J2") (pin "19") (pinfunction "19_19") (pintype "passive"))
      (node (ref "J2") (pin "7") (pinfunction "7_7") (pintype "passive"))
      (node (ref "L2") (pin "2") (pinfunction "2_2") (pintype "passive"))
      (node (ref "R66") (pin "1") (pinfunction "1_1") (pintype "passive"))
      (node (ref "R76") (pin "2") (pinfunction "2_2") (pintype "passive"))
      (node (ref "U12") (pin "3") (pinfunction "VCC_3") (pintype "power_in"))
    )
    (net (code "3") (name "+12V") (class "Default")
      (node (ref "C1") (pin "1") (pinfunction "1_1") (pintype "passive"))
      (node (ref "C81") (pin "2") (pinfunction "2_2") (pintype "passive"))
      (node (ref "C84") (pin "2") (pinfunction "2_2") (pintype "passive"))
      (node (ref "J2") (pin "24") (pinfunction "24_24") (pintype "passive"))
      (node (ref "L1") (pin "2") (pinfunction "2_2") (pintype "passive"))
      (node (ref "R70") (pin "2") (pinfunction "2_2") (pintype "passive"))
      (node (ref "U8") (pin "3") (pinfunction "EN_3") (pintype "passive"))
      (node (ref "U8") (pin "4") (pinfunction "VIN_4") (pintype "passive"))
      (node (ref "U9") (pin "3") (pinfunction "EN_3") (pintype "passive"))
      (node (ref "U9") (pin "4") (pinfunction "VIN_4") (pintype "passive"))
    )
    (net (code "4") (name "/ADC") (class "Default")
      (node (ref "J2") (pin "20") (pinfunction "20_20") (pintype "passive"))
      (node (ref "U10") (pin "25") (pinfunction "PC5_25") (pintype "passive"))
    )
    (net (code "5") (name "/CANH") (class "Default")
      (node (ref "J2") (pin "14") (pinfunction "14_14") (pintype "passive"))
      (node (ref "U12") (pin "7") (pinfunction "CANH_7") (pintype "passive"))
    )
    (net (code "6") (name "/CANL") (class "Default")
      (node (ref "J2") (pin "13") (pinfunction "13_13") (pintype "passive"))
      (node (ref "U12") (pin "6") (pinfunction "CANL_6") (pintype "passive"))
    )
    (net (code "7") (name "/CAN_RX") (class "Default")
      (node (ref "U10") (pin "61") (pinfunction "PB8_61") (pintype "passive"))
      (node (ref "U12") (pin "4") (pinfunction "RXD_4") (pintype "passive"))
    )
    (net (code "8") (name "/CAN_TX") (class "Default")
      (node (ref "U10") (pin "62") (pinfunction "PB9_62") (pintype "passive"))
      (node (ref "U12") (pin "1") (pinfunction "TXD_1") (pintype "passive"))
    )
    (net (code "9") (name "/DISABLE") (class "Default")
      (node (ref "U10") (pin "28") (pinfunction "PB2_28") (pintype "passive"))
    )
    (net (code "10") (name "/DM") (class "Default")
      (node (ref "J2") (pin "9") (pinfunction "9_9") (pintype "passive"))
      (node (ref "U11") (pin "4") (pinfunction "I/O2_2_4") (pintype "passive"))
    )
    (net (code "11") (name "/DP") (class "Default")
      (node (ref "J2") (pin "10") (pinfunction "10_10") (pintype "passive"))
      (node (ref "U11") (pin "6") (pinfunction "I/O1_2_6") (pintype "passive"))
    )
    (net (code "12") (name "/ENCO_COS") (class "Default")
      (node (ref "J2") (pin "3") (pinfunction "3_3") (pintype "passive"))
    )
    (net (code "13") (name "/ENCO_SIN") (class "Default")
      (node (ref "J2") (pin "2") (pinfunction "2_2") (pintype "passive"))
    )
    (net (code "14") (name "/HALL_U") (class "Default")
      (node (ref "J2") (pin "16") (pinfunction "16_16") (pintype "passive"))
      (node (ref "R80") (pin "1") (pinfunction "1_1") (pintype "passive"))
      (node (ref "U10") (pin "37") (pinfunction "PC6_37") (pintype "passive"))
    )
    (net (code "15") (name "/HALL_V") (class "Default")
      (node (ref "J2") (pin "17") (pinfunction "17_17") (pintype "passive"))
      (node (ref "R81") (pin "1") (pinfunction "1_1") (pintype "passive"))
      (node (ref "U10") (pin "38") (pinfunction "PC7_38") (pintype "passive"))
    )
    (net (code "16") (name "/HALL_W") (class "Default")
      (node (ref "J2") (pin "18") (pinfunction "18_18") (pintype "passive"))
      (node (ref "R82") (pin "1") (pinfunction "1_1") (pintype "passive"))
      (node (ref "U10") (pin "39") (pinfunction "PC8_39") (pintype "passive"))
    )
    (net (code "17") (name "/ISENSE_U") (class "Default")
      (node (ref "R1") (pin "2") (pinfunction "2_2") (pintype "passive"))
      (node (ref "U10") (pin "8") (pinfunction "PC0_8") (pintype "passive"))
    )
    (net (code "18") (name "/ISENSE_V") (class "Default")
      (node (ref "R2") (pin "2") (pinfunction "2_2") (pintype "passive"))
      (node (ref "U10") (pin "9") (pinfunction "PC1_9") (pintype "passive"))
    )
    (net (code "19") (name "/ISENSE_W") (class "Default")
      (node (ref "R3") (pin "2") (pinfunction "2_2") (pintype "passive"))
      (node (ref "U10") (pin "10") (pinfunction "PC2_10") (pintype "passive"))
    )
    (net (code "20") (name "/LED_GREEN") (class "Default")
      (node (ref "R74") (pin "2") (pinfunction "2_2") (pintype "passive"))
      (node (ref "U10") (pin "57") (pinfunction "PB5_57") (pintype "passive"))
    )
    (net (code "21") (name "/LED_RED") (class "Default")
      (node (ref "R73") (pin "2") (pinfunction "2_2") (pintype "passive"))
      (node (ref "U10") (pin "59") (pinfunction "PB7_59") (pintype "passive"))
    )
    (net (code "22") (name "/MISO_ADC_EXT2") (class "Default")
      (node (ref "U10") (pin "22") (pinfunction "PA6_22") (pintype "passive"))
    )
    (net (code "23") (name "/NRST") (class "Default")
      (node (ref "C92") (pin "2") (pinfunction "2_2") (pintype "passive"))
      (node (ref "J10") (pin "5") (pinfunction "5_5") (pintype "passive"))
      (node (ref "J2") (pin "23") (pinfunction "23_23") (pintype "passive"))
      (node (ref "R77") (pin "1") (pinfunction "1_1") (pintype "passive"))
      (node (ref "U10") (pin "7") (pinfunction "NRST_7") (pintype "passive"))
    )
    (net (code "24") (name "/OSC1") (class "Default")
      (node (ref "C87") (pin "2") (pinfunction "2_2") (pintype "passive"))
      (node (ref "U10") (pin "5") (pinfunction "PH0_5") (pintype "passive"))
      (node (ref "Y1") (pin "1") (pinfunction "1_1") (pintype "passive"))
    )
    (net (code "25") (name "/OSC2") (class "Default")
      (node (ref "C93") (pin "1") (pinfunction "1_1") (pintype "passive"))
      (node (ref "U10") (pin "6") (pinfunction "PH1_6") (pintype "passive"))
      (node (ref "Y1") (pin "3") (pinfunction "2_3") (pintype "passive"))
    )
    (net (code "26") (name "/OUT_U") (class "Default")
      (node (ref "U1") (pin "1") (pinfunction "IN-_1") (pintype "passive"))
    )
    (net (code "27") (name "/OUT_V") (class "Default")
      (node (ref "U2") (pin "1") (pinfunction "IN-_1") (pintype "passive"))
    )
    (net (code "28") (name "/OUT_W") (class "Default")
      (node (ref "U3") (pin "1") (pinfunction "IN-_1") (pintype "passive"))
    )
    (net (code "29") (name "/PHASE_U") (class "Default")
      (node (ref "R4") (pin "2") (pinfunction "2_2") (pintype "passive"))
      (node (ref "U1") (pin "8") (pinfunction "IN+_8") (pintype "passive"))
    )
    (net (code "30") (name "/PHASE_V") (class "Default")
      (node (ref "R5") (pin "2") (pinfunction "2_2") (pintype "passive"))
      (node (ref "U2") (pin "8") (pinfunction "IN+_8") (pintype "passive"))
    )
    (net (code "31") (name "/PHASE_W") (class "Default")
      (node (ref "R6") (pin "2") (pinfunction "2_2") (pintype "passive"))
      (node (ref "U3") (pin "8") (pinfunction "IN+_8") (pintype "passive"))
    )
    (net (code "32") (name "/PWM_U_HIGH") (class "Default")
      (node (ref "U10") (pin "41") (pinfunction "PA8_41") (pintype "passive"))
    )
    (net (code "33") (name "/PWM_U_LOW") (class "Default")
      (node (ref "U10") (pin "34") (pinfunction "PB13_34") (pintype "passive"))
    )
    (net (code "34") (name "/PWM_V_HIGH") (class "Default")
      (node (ref "U10") (pin "42") (pinfunction "PA9_42") (pintype "passive"))
    )
    (net (code "35") (name "/PWM_V_LOW") (class "Default")
      (node (ref "U10") (pin "35") (pinfunction "PB14_35") (pintype "passive"))
    )
    (net (code "36") (name "/PWM_W_HIGH") (class "Default")
      (node (ref "U10") (pin "43") (pinfunction "PA10_43") (pintype "passive"))
    )
    (net (code "37") (name "/PWM_W_LOW") (class "Default")
      (node (ref "U10") (pin "36") (pinfunction "PB15_36") (pintype "passive"))
    )
    (net (code "38") (name "/RC_PWM") (class "Default")
      (node (ref "J2") (pin "22") (pinfunction "22_22") (pintype "passive"))
      (node (ref "R83") (pin "1") (pinfunction "1_1") (pintype "passive"))
    )
    (net (code "39") (name "/RX_SDA_NSS") (class "Default")
      (node (ref "J2") (pin "6") (pinfunction "6_6") (pintype "passive"))
      (node (ref "U10") (pin "20") (pinfunction "PA4_20") (pintype "passive"))
      (node (ref "U10") (pin "30") (pinfunction "PB11_30") (pintype "passive"))
    )
    (net (code "40") (name "/SCK_ADC_EXT") (class "Default")
      (node (ref "U10") (pin "21") (pinfunction "PA5_21") (pintype "passive"))
    )
    (net (code "41") (name "/SERVO") (class "Default")
      (node (ref "C94") (pin "2") (pinfunction "2_2") (pintype "passive"))
      (node (ref "R83") (pin "2") (pinfunction "2_2") (pintype "passive"))
      (node (ref "U10") (pin "58") (pinfunction "PB6_58") (pintype "passive"))
    )
    (net (code "42") (name "/SWCLK") (class "Default")
      (node (ref "J10") (pin "2") (pinfunction "2_2") (pintype "passive"))
      (node (ref "J2") (pin "25") (pinfunction "25_25") (pintype "passive"))
      (node (ref "U10") (pin "49") (pinfunction "PA14_49") (pintype "passive"))
    )
    (net (code "43") (name "/SWDIO") (class "Default")
      (node (ref "J10") (pin "4") (pinfunction "4_4") (pintype "passive"))
      (node (ref "J2") (pin "26") (pinfunction "26_26") (pintype "passive"))
      (node (ref "U10") (pin "46") (pinfunction "PA13_46") (pintype "passive"))
    )
    (net (code "44") (name "/TEMP_MOTOR") (class "Default")
      (node (ref "J2") (pin "15") (pinfunction "15_15") (pintype "passive"))
      (node (ref "U10") (pin "24") (pinfunction "PC4_24") (pintype "passive"))
    )
    (net (code "45") (name "/TEMP_U") (class "Default")
      (node (ref "C9") (pin "2") (pinfunction "2_2") (pintype "passive"))
      (node (ref "R12") (pin "2") (pinfunction "2_2") (pintype "passive"))
      (node (ref "U10") (pin "17") (pinfunction "PA3_17") (pintype "passive"))
    )
    (net (code "46") (name "/TEMP_V") (class "Default")
      (node (ref "C10") (pin "2") (pinfunction "2_2") (pintype "passive"))
      (node (ref "R13") (pin "2") (pinfunction "2_2") (pintype "passive"))
      (node (ref "U10") (pin "26") (pinfunction "PB0_26") (pintype "passive"))
    )
    (net (code "47") (name "/TEMP_W") (class "Default")
      (node (ref "C11") (pin "2") (pinfunction "2_2") (pintype "passive"))
      (node (ref "R14") (pin "2") (pinfunction "2_2") (pintype "passive"))
      (node (ref "U10") (pin "27") (pinfunction "PB1_27") (pintype "passive"))
    )
    (net (code "48") (name "/TX_SCL_MOSI") (class "Default")
      (node (ref "J2") (pin "5") (pinfunction "5_5") (pintype "passive"))
      (node (ref "U10") (pin "23") (pinfunction "PA7_23") (pintype "passive"))
      (node (ref "U10") (pin "29") (pinfunction "PB10_29") (pintype "passive"))
    )
    (net (code "49") (name "/UART_RX") (class "Default")
      (node (ref "U10") (pin "52") (pinfunction "PC11_52") (pintype "passive"))
    )
    (net (code "50") (name "/UART_TX") (class "Default")
      (node (ref "U10") (pin "51") (pinfunction "PC10_51") (pintype "passive"))
    )
    (net (code "51") (name "/USB_DM") (class "Default")
      (node (ref "R79") (pin "1") (pinfunction "1_1") (pintype "passive"))
      (node (ref "U10") (pin "44") (pinfunction "PA11_44") (pintype "passive"))
    )
    (net (code "52") (name "/USB_DP") (class "Default")
      (node (ref "R78") (pin "1") (pinfunction "1_1") (pintype "passive"))
      (node (ref "U10") (pin "45") (pinfunction "PA12_45") (pintype "passive"))
    )
    (net (code "53") (name "/VCAP1") (class "Default")
      (node (ref "C90") (pin "2") (pinfunction "2_2") (pintype "passive"))
      (node (ref "U10") (pin "31") (pinfunction "VCAP_1_31") (pintype "passive"))
    )
    (net (code "54") (name "/VCAP2") (class "Default")
      (node (ref "C91") (pin "2") (pinfunction "2_2") (pintype "passive"))
      (node (ref "U10") (pin "47") (pinfunction "VCAP_2_47") (pintype "passive"))
    )
    (net (code "55") (name "/VSENSE") (class "Default")
      (node (ref "R11") (pin "2") (pinfunction "2_2") (pintype "passive"))
      (node (ref "R7") (pin "1") (pinfunction "1_1") (pintype "passive"))
      (node (ref "U10") (pin "11") (pinfunction "PC3_11") (pintype "passive"))
    )
    (net (code "56") (name "/VSENSE_U") (class "Default")
      (node (ref "R4") (pin "1") (pinfunction "1_1") (pintype "passive"))
      (node (ref "R8") (pin "2") (pinfunction "2_2") (pintype "passive"))
      (node (ref "U10") (pin "14") (pinfunction "PA0_WKUP_14") (pintype "passive"))
    )
    (net (code "57") (name "/VSENSE_V") (class "Default")
      (node (ref "R5") (pin "1") (pinfunction "1_1") (pintype "passive"))
      (node (ref "R9") (pin "2") (pinfunction "2_2") (pintype "passive"))
      (node (ref "U10") (pin "15") (pinfunction "PA1_15") (pintype "passive"))
    )
    (net (code "58") (name "/VSENSE_W") (class "Default")
      (node (ref "R10") (pin "2") (pinfunction "2_2") (pintype "passive"))
      (node (ref "R6") (pin "1") (pinfunction "1_1") (pintype "passive"))
      (node (ref "U10") (pin "16") (pinfunction "PA2_16") (pintype "passive"))
    )
    (net (code "59") (name "GND") (class "Default")
      (node (ref "C1") (pin "2") (pinfunction "2_2") (pintype "passive"))
      (node (ref "C10") (pin "1") (pinfunction "1_1") (pintype "passive"))
      (node (ref "C11") (pin "1") (pinfunction "1_1") (pintype "passive"))
      (node (ref "C12") (pin "2") (pinfunction "2_2") (pintype "passive"))
      (node (ref "C2") (pin "2") (pinfunction "2_2") (pintype "passive"))
      (node (ref "C3") (pin "2") (pinfunction "2_2") (pintype "passive"))
      (node (ref "C4") (pin "1") (pinfunction "1_1") (pintype "passive"))
      (node (ref "C43") (pin "2") (pinfunction "2_2") (pintype "passive"))
      (node (ref "C44") (pin "2") (pinfunction "2_2") (pintype "passive"))
      (node (ref "C45") (pin "2") (pinfunction "2_2") (pintype "passive"))
      (node (ref "C46") (pin "2") (pinfunction "2_2") (pintype "passive"))
      (node (ref "C47") (pin "2") (pinfunction "2_2") (pintype "passive"))
      (node (ref "C48") (pin "2") (pinfunction "2_2") (pintype "passive"))
      (node (ref "C49") (pin "2") (pinfunction "2_2") (pintype "passive"))
      (node (ref "C5") (pin "1") (pinfunction "1_1") (pintype "passive"))
      (node (ref "C6") (pin "1") (pinfunction "1_1") (pintype "passive"))
      (node (ref "C61") (pin "1") (pinfunction "1_1") (pintype "passive"))
      (node (ref "C62") (pin "1") (pinfunction "1_1") (pintype "passive"))
      (node (ref "C63") (pin "1") (pinfunction "1_1") (pintype "passive"))
      (node (ref "C64") (pin "1") (pinfunction "1_1") (pintype "passive"))
      (node (ref "C65") (pin "1") (pinfunction "1_1") (pintype "passive"))
      (node (ref "C66") (pin "1") (pinfunction "1_1") (pintype "passive"))
      (node (ref "C67") (pin "1") (pinfunction "1_1") (pintype "passive"))
      (node (ref "C68") (pin "1") (pinfunction "1_1") (pintype "passive"))
      (node (ref "C69") (pin "1") (pinfunction "1_1") (pintype "passive"))
      (node (ref "C7") (pin "2") (pinfunction "2_2") (pintype "passive"))
      (node (ref "C70") (pin "1") (pinfunction "1_1") (pintype "passive"))
      (node (ref "C71") (pin "1") (pinfunction "1_1") (pintype "passive"))
      (node (ref "C76") (pin "1") (pinfunction "1_1") (pintype "passive"))
      (node (ref "C77") (pin "1") (pinfunction "1_1") (pintype "passive"))
      (node (ref "C78") (pin "1") (pinfunction "1_1") (pintype "passive"))
      (node (ref "C79") (pin "1") (pinfunction "1_1") (pintype "passive"))
      (node (ref "C8") (pin "2") (pinfunction "2_2") (pintype "passive"))
      (node (ref "C81") (pin "1") (pinfunction "1_1") (pintype "passive"))
      (node (ref "C82") (pin "1") (pinfunction "1_1") (pintype "passive"))
      (node (ref "C84") (pin "1") (pinfunction "1_1") (pintype "passive"))
      (node (ref "C85") (pin "1") (pinfunction "1_1") (pintype "passive"))
      (node (ref "C86") (pin "1") (pinfunction "1_1") (pintype "passive"))
      (node (ref "C87") (pin "1") (pinfunction "1_1") (pintype "passive"))
      (node (ref "C88") (pin "1") (pinfunction "1_1") (pintype "passive"))
      (node (ref "C89") (pin "1") (pinfunction "1_1") (pintype "passive"))
      (node (ref "C9") (pin "1") (pinfunction "1_1") (pintype "passive"))
      (node (ref "C90") (pin "1") (pinfunction "1_1") (pintype "passive"))
      (node (ref "C91") (pin "1") (pinfunction "1_1") (pintype "passive"))
      (node (ref "C92") (pin "1") (pinfunction "1_1") (pintype "passive"))
      (node (ref "C93") (pin "2") (pinfunction "2_2") (pintype "passive"))
      (node (ref "C94") (pin "1") (pinfunction "1_1") (pintype "passive"))
      (node (ref "D10") (pin "1") (pinfunction "K_1") (pintype "passive"))
      (node (ref "D11") (pin "1") (pinfunction "K_1") (pintype "passive"))
      (node (ref "D12") (pin "1") (pinfunction "K_1") (pintype "passive"))
      (node (ref "J10") (pin "3") (pinfunction "3_3") (pintype "passive"))
      (node (ref "J2") (pin "12") (pinfunction "12_12") (pintype "passive"))
      (node (ref "J2") (pin "4") (pinfunction "4_4") (pintype "passive"))
      (node (ref "J2") (pin "8") (pinfunction "8_8") (pintype "passive"))
      (node (ref "R10") (pin "1") (pinfunction "1_1") (pintype "passive"))
      (node (ref "R11") (pin "1") (pinfunction "1_1") (pintype "passive"))
      (node (ref "R12") (pin "1") (pinfunction "1_1") (pintype "passive"))
      (node (ref "R13") (pin "1") (pinfunction "1_1") (pintype "passive"))
      (node (ref "R14") (pin "1") (pinfunction "1_1") (pintype "passive"))
      (node (ref "R67") (pin "2") (pinfunction "2_2") (pintype "passive"))
      (node (ref "R69") (pin "2") (pinfunction "2_2") (pintype "passive"))
      (node (ref "R71") (pin "1") (pinfunction "1_1") (pintype "passive"))
      (node (ref "R72") (pin "1") (pinfunction "1_1") (pintype "passive"))
      (node (ref "R8") (pin "1") (pinfunction "1_1") (pintype "passive"))
      (node (ref "R9") (pin "1") (pinfunction "1_1") (pintype "passive"))
      (node (ref "U1") (pin "2") (pinfunction "GND_2") (pintype "passive"))
      (node (ref "U1") (pin "7") (pinfunction "REF1_7") (pintype "passive"))
      (node (ref "U10") (pin "13") (pinfunction "VDDA_13") (pintype "passive"))
      (node (ref "U10") (pin "18") (pinfunction "VSS_1_18") (pintype "passive"))
      (node (ref "U10") (pin "60") (pinfunction "BOOT0_60") (pintype "passive"))
      (node (ref "U10") (pin "63") (pinfunction "VSS_2_63") (pintype "passive"))
      (node (ref "U11") (pin "2") (pinfunction "GND_2") (pintype "passive"))
      (node (ref "U12") (pin "2") (pinfunction "GND_2") (pintype "passive"))
      (node (ref "U12") (pin "8") (pinfunction "S_8") (pintype "passive"))
      (node (ref "U12") (pin "9") (pinfunction "PAD_9") (pintype "passive"))
      (node (ref "U2") (pin "2") (pinfunction "GND_2") (pintype "passive"))
      (node (ref "U2") (pin "7") (pinfunction "REF1_7") (pintype "passive"))
      (node (ref "U3") (pin "2") (pinfunction "GND_2") (pintype "passive"))
      (node (ref "U3") (pin "7") (pinfunction "REF1_7") (pintype "passive"))
      (node (ref "U7") (pin "1") (pinfunction "GND_1") (pintype "passive"))
      (node (ref "U7") (pin "9") (pinfunction "EP_9") (pintype "passive"))
      (node (ref "U8") (pin "5") (pinfunction "PGND_5") (pintype "passive"))
      (node (ref "U8") (pin "8") (pinfunction "AGND_8") (pintype "passive"))
      (node (ref "U8") (pin "9") (pinfunction "EP_9") (pintype "passive"))
      (node (ref "U9") (pin "5") (pinfunction "PGND_5") (pintype "passive"))
      (node (ref "U9") (pin "8") (pinfunction "AGND_8") (pintype "passive"))
      (node (ref "U9") (pin "9") (pinfunction "EP_9") (pintype "passive"))
      (node (ref "Y1") (pin "2") (pinfunction "GND_2") (pintype "power_in"))
      (node (ref "Y1") (pin "4") (pinfunction "GND_4") (pintype "power_in"))
    )
    (net (code "60") (name "Net-(D10-A)") (class "Default")
      (node (ref "D10") (pin "2") (pinfunction "A_2") (pintype "passive"))
      (node (ref "R73") (pin "1") (pinfunction "1_1") (pintype "passive"))
    )
    (net (code "61") (name "Net-(D11-A)") (class "Default")
      (node (ref "D11") (pin "2") (pinfunction "A_2") (pintype "passive"))
      (node (ref "R74") (pin "1") (pinfunction "1_1") (pintype "passive"))
    )
    (net (code "62") (name "Net-(D12-A)") (class "Default")
      (node (ref "D12") (pin "2") (pinfunction "A_2") (pintype "passive"))
      (node (ref "R75") (pin "1") (pinfunction "1_1") (pintype "passive"))
    )
    (net (code "63") (name "Net-(U1-OUT)") (class "Default")
      (node (ref "R1") (pin "1") (pinfunction "1_1") (pintype "passive"))
      (node (ref "U1") (pin "5") (pinfunction "OUT_5") (pintype "passive"))
    )
    (net (code "64") (name "Net-(U2-OUT)") (class "Default")
      (node (ref "R2") (pin "1") (pinfunction "1_1") (pintype "passive"))
      (node (ref "U2") (pin "5") (pinfunction "OUT_5") (pintype "passive"))
    )
    (net (code "65") (name "Net-(U3-OUT)") (class "Default")
      (node (ref "R3") (pin "1") (pinfunction "1_1") (pintype "passive"))
      (node (ref "U3") (pin "5") (pinfunction "OUT_5") (pintype "passive"))
    )
    (net (code "66") (name "Net-(U7-BST)") (class "Default")
      (node (ref "C72") (pin "1") (pinfunction "1_1") (pintype "passive"))
      (node (ref "U7") (pin "7") (pinfunction "BST_7") (pintype "passive"))
    )
    (net (code "67") (name "Net-(U7-FB)") (class "Default")
      (node (ref "R70") (pin "1") (pinfunction "1_1") (pintype "passive"))
      (node (ref "R72") (pin "2") (pinfunction "2_2") (pintype "passive"))
      (node (ref "U7") (pin "5") (pinfunction "FB_5") (pintype "passive"))
    )
    (net (code "68") (name "Net-(U7-RON)") (class "Default")
      (node (ref "R71") (pin "2") (pinfunction "2_2") (pintype "passive"))
      (node (ref "U7") (pin "4") (pinfunction "RON_4") (pintype "passive"))
    )
    (net (code "69") (name "Net-(U7-SW)") (class "Default")
      (node (ref "C72") (pin "2") (pinfunction "2_2") (pintype "passive"))
      (node (ref "L1") (pin "1") (pinfunction "1_1") (pintype "passive"))
      (node (ref "U7") (pin "8") (pinfunction "SW_8") (pintype "passive"))
    )
    (net (code "70") (name "Net-(U8-BOOST)") (class "Default")
      (node (ref "C74") (pin "2") (pinfunction "2_2") (pintype "passive"))
      (node (ref "U8") (pin "7") (pinfunction "BOOST_7") (pintype "passive"))
    )
    (net (code "71") (name "Net-(U8-SW)") (class "Default")
      (node (ref "C74") (pin "1") (pinfunction "1_1") (pintype "passive"))
      (node (ref "L2") (pin "1") (pinfunction "1_1") (pintype "passive"))
      (node (ref "U8") (pin "6") (pinfunction "SW_6") (pintype "passive"))
    )
    (net (code "72") (name "Net-(U8-VCC)") (class "Default")
      (node (ref "C85") (pin "2") (pinfunction "2_2") (pintype "passive"))
      (node (ref "U8") (pin "2") (pinfunction "VCC_2") (pintype "passive"))
    )
    (net (code "73") (name "Net-(U8-VFB)") (class "Default")
      (node (ref "R66") (pin "2") (pinfunction "2_2") (pintype "passive"))
      (node (ref "R67") (pin "1") (pinfunction "1_1") (pintype "passive"))
      (node (ref "U8") (pin "1") (pinfunction "VFB_1") (pintype "passive"))
    )
    (net (code "74") (name "Net-(U9-BOOST)") (class "Default")
      (node (ref "C75") (pin "2") (pinfunction "2_2") (pintype "passive"))
      (node (ref "U9") (pin "7") (pinfunction "BOOST_7") (pintype "passive"))
    )
    (net (code "75") (name "Net-(U9-SW)") (class "Default")
      (node (ref "C75") (pin "1") (pinfunction "1_1") (pintype "passive"))
      (node (ref "L3") (pin "1") (pinfunction "1_1") (pintype "passive"))
      (node (ref "U9") (pin "6") (pinfunction "SW_6") (pintype "passive"))
    )
    (net (code "76") (name "Net-(U9-VCC)") (class "Default")
      (node (ref "C86") (pin "2") (pinfunction "2_2") (pintype "passive"))
      (node (ref "U9") (pin "2") (pinfunction "VCC_2") (pintype "passive"))
    )
    (net (code "77") (name "Net-(U9-VFB)") (class "Default")
      (node (ref "R68") (pin "2") (pinfunction "2_2") (pintype "passive"))
      (node (ref "R69") (pin "1") (pinfunction "1_1") (pintype "passive"))
      (node (ref "U9") (pin "1") (pinfunction "VFB_1") (pintype "passive"))
    )
    (net (code "78") (name "Net-(U11-I{slash}O1_1)") (class "Default")
      (node (ref "R78") (pin "2") (pinfunction "2_2") (pintype "passive"))
      (node (ref "U11") (pin "1") (pinfunction "I/O1_1_1") (pintype "passive"))
    )
    (net (code "79") (name "Net-(U11-I{slash}O2_1)") (class "Default")
      (node (ref "R79") (pin "2") (pinfunction "2_2") (pintype "passive"))
      (node (ref "U11") (pin "3") (pinfunction "I/O2_1_3") (pintype "passive"))
    )
    (net (code "80") (name "Net-(U11-VBUS)") (class "Default")
      (node (ref "R76") (pin "1") (pinfunction "1_1") (pintype "passive"))
      (node (ref "U11") (pin "5") (pinfunction "VBUS_5") (pintype "passive"))
    )
    (net (code "81") (name "VDDA") (class "Default")
      (node (ref "C76") (pin "2") (pinfunction "2_2") (pintype "passive"))
      (node (ref "C77") (pin "2") (pinfunction "2_2") (pintype "passive"))
      (node (ref "C78") (pin "2") (pinfunction "2_2") (pintype "passive"))
      (node (ref "FL") (pin "2") (pinfunction "2_2") (pintype "passive"))
      (node (ref "U10") (pin "12") (pinfunction "VSSA_12") (pintype "passive"))
    )
    (net (code "82") (name "VIN+") (class "Default")
      (node (ref "C12") (pin "1") (pinfunction "1_1") (pintype "passive"))
      (node (ref "C43") (pin "1") (pinfunction "1_1") (pintype "passive"))
      (node (ref "C44") (pin "1") (pinfunction "1_1") (pintype "passive"))
      (node (ref "C45") (pin "1") (pinfunction "1_1") (pintype "passive"))
      (node (ref "C46") (pin "1") (pinfunction "1_1") (pintype "passive"))
      (node (ref "C47") (pin "1") (pinfunction "1_1") (pintype "passive"))
      (node (ref "C48") (pin "1") (pinfunction "1_1") (pintype "passive"))
      (node (ref "C49") (pin "1") (pinfunction "1_1") (pintype "passive"))
      (node (ref "C7") (pin "1") (pinfunction "1_1") (pintype "passive"))
      (node (ref "C71") (pin "2") (pinfunction "2_2") (pintype "passive"))
      (node (ref "C8") (pin "1") (pinfunction "1_1") (pintype "passive"))
      (node (ref "R7") (pin "2") (pinfunction "2_2") (pintype "passive"))
      (node (ref "U7") (pin "2") (pinfunction "VIN_2") (pintype "passive"))
      (node (ref "U7") (pin "3") (pinfunction "EN/UVLO_3") (pintype "passive"))
    )
    (net (code "83") (name "unconnected-(J2-Pad21)") (class "Default")
      (node (ref "J2") (pin "21") (pinfunction "21_21") (pintype "passive"))
    )
    (net (code "84") (name "unconnected-(U7-PGOOD-Pad6)") (class "Default")
      (node (ref "U7") (pin "6") (pinfunction "PGOOD_6") (pintype "passive"))
    )
    (net (code "85") (name "unconnected-(U10-PA15-Pad50)") (class "Default")
      (node (ref "U10") (pin "50") (pinfunction "PA15_50") (pintype "passive"))
    )
    (net (code "86") (name "unconnected-(U10-PB3-Pad55)") (class "Default")
      (node (ref "U10") (pin "55") (pinfunction "PB3_55") (pintype "passive"))
    )
    (net (code "87") (name "unconnected-(U10-PB4-Pad56)") (class "Default")
      (node (ref "U10") (pin "56") (pinfunction "PB4_56") (pintype "passive"))
    )
    (net (code "88") (name "unconnected-(U10-PB12-Pad33)") (class "Default")
      (node (ref "U10") (pin "33") (pinfunction "PB12_33") (pintype "passive"))
    )
    (net (code "89") (name "unconnected-(U10-PC9-Pad40)") (class "Default")
      (node (ref "U10") (pin "40") (pinfunction "PC9_40") (pintype "passive"))
    )
    (net (code "90") (name "unconnected-(U10-PC12-Pad53)") (class "Default")
      (node (ref "U10") (pin "53") (pinfunction "PC12_53") (pintype "passive"))
    )
    (net (code "91") (name "unconnected-(U10-PC13-Pad2)") (class "Default")
      (node (ref "U10") (pin "2") (pinfunction "PC13_2") (pintype "passive"))
    )
    (net (code "92") (name "unconnected-(U10-PC14-Pad3)") (class "Default")
      (node (ref "U10") (pin "3") (pinfunction "PC14_3") (pintype "passive"))
    )
    (net (code "93") (name "unconnected-(U10-PC15-Pad4)") (class "Default")
      (node (ref "U10") (pin "4") (pinfunction "PC15_4") (pintype "passive"))
    )
    (net (code "94") (name "unconnected-(U10-PD2-Pad54)") (class "Default")
      (node (ref "U10") (pin "54") (pinfunction "PD2_54") (pintype "passive"))
    )
  )
)
